# SheildLattePanda.net
KiCad netlist of a schematic drawn in Altium Designer
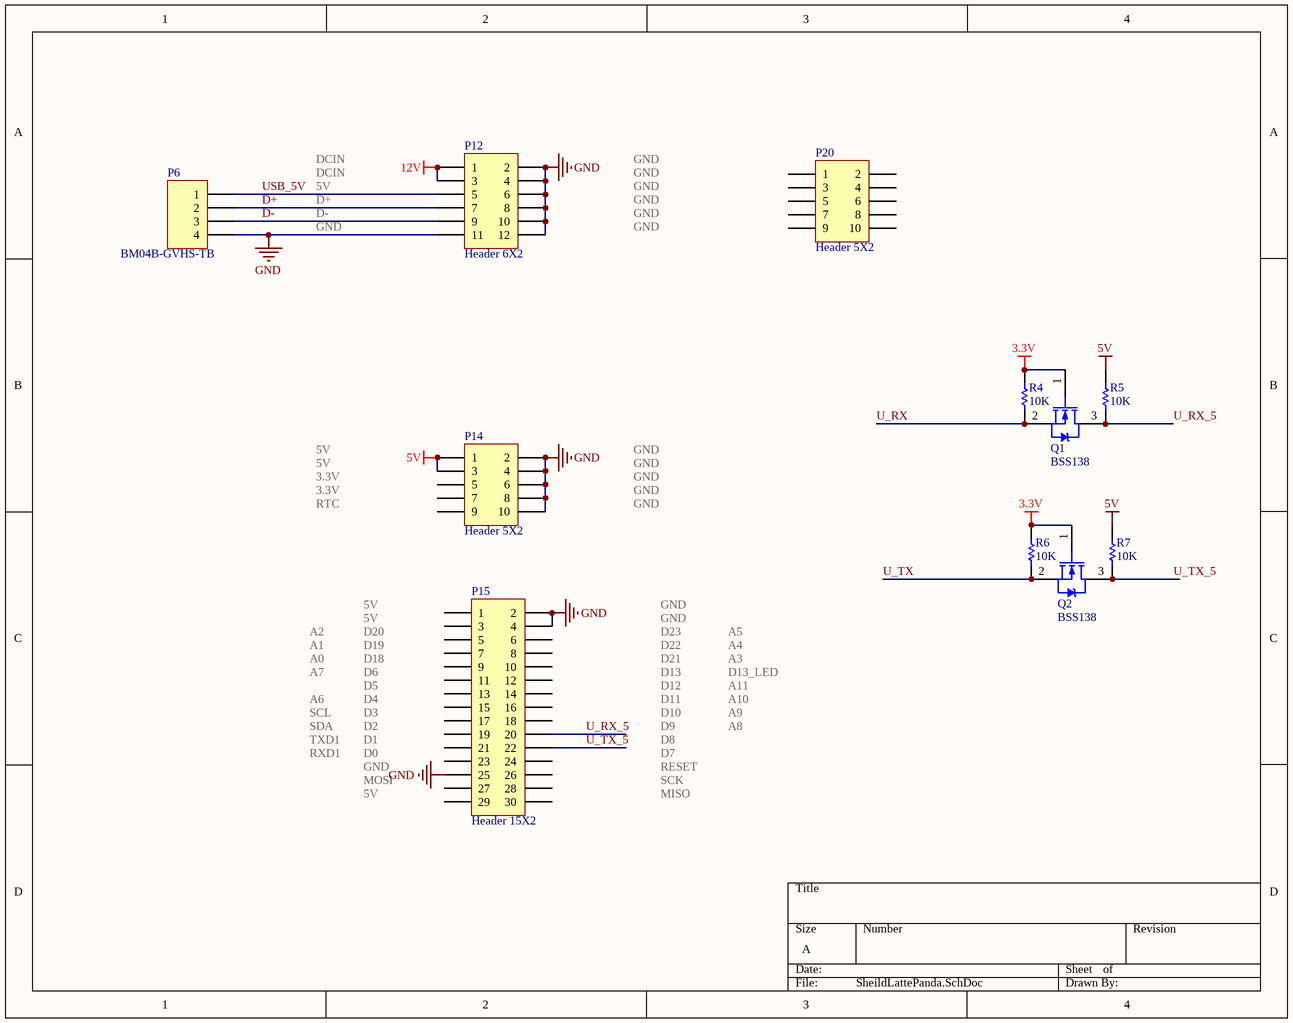
[diagram p0: SheildLattePanda.SchDoc]

(export (version "E")
  (design (tool "Eeschema 10.0.6"))
  (components
    (comp (ref "P6")
      (value "BM04B-GVHS-TB")
      (footprint "CONN-SM04B-GHSV-TB - INVERTED")
      (description "Conn Header SMD 4POS 1.25MM")
      (fields (field (name "MANUFACTURER") "JST"))
      (libsource (lib "Miscellaneous Connectors") (part "Header 4"))
    )
    (comp (ref "P12")
      (value "Header 6X2")
      (footprint "CONN-2x6_0_1INCH_SMT - duplicate - duplicate")
      (description "Conn Unshrouded Header HDR 12 POS 2.54mm Solder ST Top Entry SMD T/R")
      (fields
        (field (name "MANUFACTURER") "Amphenol ICC / FCI")
        (field (name "MANUFACTURER PART NUMBER") "10129383-912002ALF")
        (field (name "PUBLISHER") "Altium Limited")
      )
      (libsource (lib "Miscellaneous Connectors") (part "Header 6X2"))
    )
    (comp (ref "P14")
      (value "Header 5X2")
      (footprint "CONN-2x5_0_1INCH_SMT - duplicate")
      (description "Btb Connector, Header, 10POS, 2ROW, 2.54MM;")
      (fields
        (field (name "MANUFACTURER") "Amphenol Communications Solutions")
        (field (name "MANUFACTURER PART NUMBER") "10129383-910002ALF")
      )
      (libsource (lib "Miscellaneous Connectors") (part "Header 5X2"))
    )
    (comp (ref "P15")
      (value "Header 15X2")
      (footprint "CONN-2x15_0_1INCH_SMT")
      (description "Header, 15-Pin, Dual row")
      (libsource (lib "Miscellaneous Connectors") (part "Header 15X2"))
    )
    (comp (ref "P20")
      (value "Header 5X2")
      (footprint "CONN-2x5_0_1INCH_SMT - duplicate")
      (description "Btb Connector, Header, 10POS, 2ROW, 2.54MM;")
      (fields
        (field (name "MANUFACTURER") "Amphenol Communications Solutions")
        (field (name "MANUFACTURER PART NUMBER") "10129383-910002ALF")
      )
      (libsource (lib "Miscellaneous Connectors") (part "Header 5X2"))
    )
    (comp (ref "Q1")
      (value "BSS138")
      (footprint "SOT-23")
      (description "N-Channel Power MOSFET")
      (libsource (lib "Miscellaneous Devices") (part "NMOS-2"))
    )
    (comp (ref "Q2")
      (value "BSS138")
      (footprint "SOT-23")
      (description "N-Channel Power MOSFET")
      (libsource (lib "Miscellaneous Devices") (part "NMOS-2"))
    )
    (comp (ref "R4")
      (value "10K")
      (footprint "R0402")
      (description "RES SMD 10 KOHM 1% 1/16W 0402")
      (fields (field (name "Comment") "Res1"))
      (libsource (lib "Miscellaneous Devices") (part "Res1"))
    )
    (comp (ref "R5")
      (value "10K")
      (footprint "R0402")
      (description "RES SMD 10 KOHM 1% 1/16W 0402")
      (fields (field (name "Comment") "Res1"))
      (libsource (lib "Miscellaneous Devices") (part "Res1"))
    )
    (comp (ref "R6")
      (value "10K")
      (footprint "R0402")
      (description "RES SMD 10 KOHM 1% 1/16W 0402")
      (fields (field (name "Comment") "Res1"))
      (libsource (lib "Miscellaneous Devices") (part "Res1"))
    )
    (comp (ref "R7")
      (value "10K")
      (footprint "R0402")
      (description "RES SMD 10 KOHM 1% 1/16W 0402")
      (fields (field (name "Comment") "Res1"))
      (libsource (lib "Miscellaneous Devices") (part "Res1"))
    )
  )
  (nets
    (net (code "1") (name "/D+") (class "Default")
      (node (ref "P12") (pin "7") (pinfunction "7_7") (pintype "passive"))
      (node (ref "P6") (pin "2") (pinfunction "2_2") (pintype "passive"))
    )
    (net (code "2") (name "/D-") (class "Default")
      (node (ref "P12") (pin "9") (pinfunction "9_9") (pintype "passive"))
      (node (ref "P6") (pin "3") (pinfunction "3_3") (pintype "passive"))
    )
    (net (code "3") (name "/USB_5V") (class "Default")
      (node (ref "P12") (pin "5") (pinfunction "5_5") (pintype "passive"))
      (node (ref "P6") (pin "1") (pinfunction "1_1") (pintype "passive"))
    )
    (net (code "4") (name "/U_RX") (class "Default")
      (node (ref "Q1") (pin "2") (pinfunction "S_2") (pintype "passive"))
      (node (ref "R4") (pin "2") (pinfunction "2_2") (pintype "passive"))
    )
    (net (code "5") (name "/U_RX_5") (class "Default")
      (node (ref "P15") (pin "20") (pinfunction "20_20") (pintype "passive"))
      (node (ref "Q1") (pin "3") (pinfunction "D_3") (pintype "passive"))
      (node (ref "R5") (pin "2") (pinfunction "2_2") (pintype "passive"))
    )
    (net (code "6") (name "/U_TX") (class "Default")
      (node (ref "Q2") (pin "2") (pinfunction "S_2") (pintype "passive"))
      (node (ref "R6") (pin "2") (pinfunction "2_2") (pintype "passive"))
    )
    (net (code "7") (name "/U_TX_5") (class "Default")
      (node (ref "P15") (pin "22") (pinfunction "22_22") (pintype "passive"))
      (node (ref "Q2") (pin "3") (pinfunction "D_3") (pintype "passive"))
      (node (ref "R7") (pin "2") (pinfunction "2_2") (pintype "passive"))
    )
    (net (code "8") (name "3.3V") (class "Default")
      (node (ref "Q1") (pin "1") (pinfunction "G_1") (pintype "passive"))
      (node (ref "Q2") (pin "1") (pinfunction "G_1") (pintype "passive"))
      (node (ref "R4") (pin "1") (pinfunction "1_1") (pintype "passive"))
      (node (ref "R6") (pin "1") (pinfunction "1_1") (pintype "passive"))
    )
    (net (code "9") (name "5V") (class "Default")
      (node (ref "P14") (pin "1") (pinfunction "1_1") (pintype "passive"))
      (node (ref "P14") (pin "3") (pinfunction "3_3") (pintype "passive"))
      (node (ref "R5") (pin "1") (pinfunction "1_1") (pintype "passive"))
      (node (ref "R7") (pin "1") (pinfunction "1_1") (pintype "passive"))
    )
    (net (code "10") (name "12V") (class "Default")
      (node (ref "P12") (pin "1") (pinfunction "1_1") (pintype "passive"))
      (node (ref "P12") (pin "3") (pinfunction "3_3") (pintype "passive"))
    )
    (net (code "11") (name "GND") (class "Default")
      (node (ref "P12") (pin "10") (pinfunction "10_10") (pintype "passive"))
      (node (ref "P12") (pin "11") (pinfunction "11_11") (pintype "passive"))
      (node (ref "P12") (pin "12") (pinfunction "12_12") (pintype "passive"))
      (node (ref "P12") (pin "2") (pinfunction "2_2") (pintype "passive"))
      (node (ref "P12") (pin "4") (pinfunction "4_4") (pintype "passive"))
      (node (ref "P12") (pin "6") (pinfunction "6_6") (pintype "passive"))
      (node (ref "P12") (pin "8") (pinfunction "8_8") (pintype "passive"))
      (node (ref "P14") (pin "10") (pinfunction "10_10") (pintype "passive"))
      (node (ref "P14") (pin "2") (pinfunction "2_2") (pintype "passive"))
      (node (ref "P14") (pin "4") (pinfunction "4_4") (pintype "passive"))
      (node (ref "P14") (pin "6") (pinfunction "6_6") (pintype "passive"))
      (node (ref "P14") (pin "8") (pinfunction "8_8") (pintype "passive"))
      (node (ref "P15") (pin "2") (pinfunction "2_2") (pintype "passive"))
      (node (ref "P15") (pin "25") (pinfunction "25_25") (pintype "passive"))
      (node (ref "P15") (pin "4") (pinfunction "4_4") (pintype "passive"))
      (node (ref "P6") (pin "4") (pinfunction "4_4") (pintype "passive"))
    )
    (net (code "12") (name "unconnected-(P14-Pad5)") (class "Default")
      (node (ref "P14") (pin "5") (pinfunction "5_5") (pintype "passive"))
    )
    (net (code "13") (name "unconnected-(P14-Pad7)") (class "Default")
      (node (ref "P14") (pin "7") (pinfunction "7_7") (pintype "passive"))
    )
    (net (code "14") (name "unconnected-(P14-Pad9)") (class "Default")
      (node (ref "P14") (pin "9") (pinfunction "9_9") (pintype "passive"))
    )
    (net (code "15") (name "unconnected-(P15-Pad1)") (class "Default")
      (node (ref "P15") (pin "1") (pinfunction "1_1") (pintype "passive"))
    )
    (net (code "16") (name "unconnected-(P15-Pad3)") (class "Default")
      (node (ref "P15") (pin "3") (pinfunction "3_3") (pintype "passive"))
    )
    (net (code "17") (name "unconnected-(P15-Pad5)") (class "Default")
      (node (ref "P15") (pin "5") (pinfunction "5_5") (pintype "passive"))
    )
    (net (code "18") (name "unconnected-(P15-Pad6)") (class "Default")
      (node (ref "P15") (pin "6") (pinfunction "6_6") (pintype "passive"))
    )
    (net (code "19") (name "unconnected-(P15-Pad7)") (class "Default")
      (node (ref "P15") (pin "7") (pinfunction "7_7") (pintype "passive"))
    )
    (net (code "20") (name "unconnected-(P15-Pad8)") (class "Default")
      (node (ref "P15") (pin "8") (pinfunction "8_8") (pintype "passive"))
    )
    (net (code "21") (name "unconnected-(P15-Pad9)") (class "Default")
      (node (ref "P15") (pin "9") (pinfunction "9_9") (pintype "passive"))
    )
    (net (code "22") (name "unconnected-(P15-Pad10)") (class "Default")
      (node (ref "P15") (pin "10") (pinfunction "10_10") (pintype "passive"))
    )
    (net (code "23") (name "unconnected-(P15-Pad11)") (class "Default")
      (node (ref "P15") (pin "11") (pinfunction "11_11") (pintype "passive"))
    )
    (net (code "24") (name "unconnected-(P15-Pad12)") (class "Default")
      (node (ref "P15") (pin "12") (pinfunction "12_12") (pintype "passive"))
    )
    (net (code "25") (name "unconnected-(P15-Pad13)") (class "Default")
      (node (ref "P15") (pin "13") (pinfunction "13_13") (pintype "passive"))
    )
    (net (code "26") (name "unconnected-(P15-Pad14)") (class "Default")
      (node (ref "P15") (pin "14") (pinfunction "14_14") (pintype "passive"))
    )
    (net (code "27") (name "unconnected-(P15-Pad15)") (class "Default")
      (node (ref "P15") (pin "15") (pinfunction "15_15") (pintype "passive"))
    )
    (net (code "28") (name "unconnected-(P15-Pad16)") (class "Default")
      (node (ref "P15") (pin "16") (pinfunction "16_16") (pintype "passive"))
    )
    (net (code "29") (name "unconnected-(P15-Pad17)") (class "Default")
      (node (ref "P15") (pin "17") (pinfunction "17_17") (pintype "passive"))
    )
    (net (code "30") (name "unconnected-(P15-Pad18)") (class "Default")
      (node (ref "P15") (pin "18") (pinfunction "18_18") (pintype "passive"))
    )
    (net (code "31") (name "unconnected-(P15-Pad19)") (class "Default")
      (node (ref "P15") (pin "19") (pinfunction "19_19") (pintype "passive"))
    )
    (net (code "32") (name "unconnected-(P15-Pad21)") (class "Default")
      (node (ref "P15") (pin "21") (pinfunction "21_21") (pintype "passive"))
    )
    (net (code "33") (name "unconnected-(P15-Pad23)") (class "Default")
      (node (ref "P15") (pin "23") (pinfunction "23_23") (pintype "passive"))
    )
    (net (code "34") (name "unconnected-(P15-Pad24)") (class "Default")
      (node (ref "P15") (pin "24") (pinfunction "24_24") (pintype "passive"))
    )
    (net (code "35") (name "unconnected-(P15-Pad26)") (class "Default")
      (node (ref "P15") (pin "26") (pinfunction "26_26") (pintype "passive"))
    )
    (net (code "36") (name "unconnected-(P15-Pad27)") (class "Default")
      (node (ref "P15") (pin "27") (pinfunction "27_27") (pintype "passive"))
    )
    (net (code "37") (name "unconnected-(P15-Pad28)") (class "Default")
      (node (ref "P15") (pin "28") (pinfunction "28_28") (pintype "passive"))
    )
    (net (code "38") (name "unconnected-(P15-Pad29)") (class "Default")
      (node (ref "P15") (pin "29") (pinfunction "29_29") (pintype "passive"))
    )
    (net (code "39") (name "unconnected-(P15-Pad30)") (class "Default")
      (node (ref "P15") (pin "30") (pinfunction "30_30") (pintype "passive"))
    )
    (net (code "40") (name "unconnected-(P20-Pad1)") (class "Default")
      (node (ref "P20") (pin "1") (pinfunction "1_1") (pintype "passive"))
    )
    (net (code "41") (name "unconnected-(P20-Pad2)") (class "Default")
      (node (ref "P20") (pin "2") (pinfunction "2_2") (pintype "passive"))
    )
    (net (code "42") (name "unconnected-(P20-Pad3)") (class "Default")
      (node (ref "P20") (pin "3") (pinfunction "3_3") (pintype "passive"))
    )
    (net (code "43") (name "unconnected-(P20-Pad4)") (class "Default")
      (node (ref "P20") (pin "4") (pinfunction "4_4") (pintype "passive"))
    )
    (net (code "44") (name "unconnected-(P20-Pad5)") (class "Default")
      (node (ref "P20") (pin "5") (pinfunction "5_5") (pintype "passive"))
    )
    (net (code "45") (name "unconnected-(P20-Pad6)") (class "Default")
      (node (ref "P20") (pin "6") (pinfunction "6_6") (pintype "passive"))
    )
    (net (code "46") (name "unconnected-(P20-Pad7)") (class "Default")
      (node (ref "P20") (pin "7") (pinfunction "7_7") (pintype "passive"))
    )
    (net (code "47") (name "unconnected-(P20-Pad8)") (class "Default")
      (node (ref "P20") (pin "8") (pinfunction "8_8") (pintype "passive"))
    )
    (net (code "48") (name "unconnected-(P20-Pad9)") (class "Default")
      (node (ref "P20") (pin "9") (pinfunction "9_9") (pintype "passive"))
    )
    (net (code "49") (name "unconnected-(P20-Pad10)") (class "Default")
      (node (ref "P20") (pin "10") (pinfunction "10_10") (pintype "passive"))
    )
  )
)
